# dv_power_chanel.net
KiCad netlist of a schematic drawn in Altium Designer
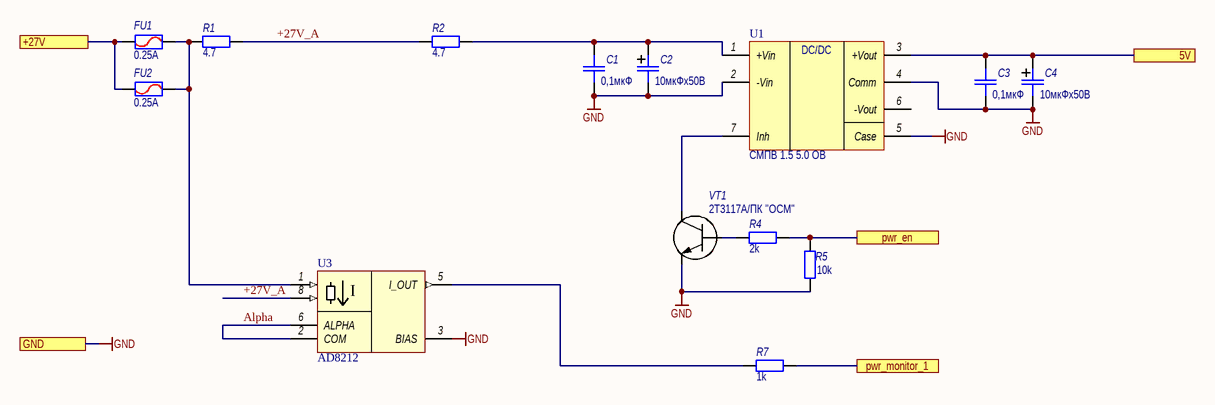
[diagram p0: dv_power_chanel_ВП.SchDoc]

(export (version "E")
  (design (tool "Eeschema 10.0.6"))
  (components
    (comp (ref "C1")
      (value "0,1мкФ")
      (footprint "SMD_0805")
      (description "Capacitor")
      (libsource (lib "Passive") (part "Capacitor"))
    )
    (comp (ref "C2")
      (value "10мкФх50В")
      (footprint "SMD_size_B")
      (description "Polarized capacitor")
      (libsource (lib "Passive") (part "Capacitor_pol"))
    )
    (comp (ref "C3")
      (value "0,1мкФ")
      (footprint "SMD_0805")
      (description "Capacitor")
      (libsource (lib "Passive") (part "Capacitor"))
    )
    (comp (ref "C4")
      (value "10мкФх50В")
      (footprint "SMD_size_B")
      (description "Polarized capacitor")
      (libsource (lib "Passive") (part "Capacitor_pol"))
    )
    (comp (ref "FU1")
      (value "0.25A")
      (footprint "VP1-2")
      (description "Предохранитель плавкий")
      (fields (field (name "Comment") "VP1-2"))
      (libsource (lib "Fuse") (part "VP1-2"))
    )
    (comp (ref "FU2")
      (value "0.25A")
      (footprint "VP1-2")
      (description "Предохранитель плавкий")
      (fields (field (name "Comment") "VP1-2"))
      (libsource (lib "Fuse") (part "VP1-2"))
    )
    (comp (ref "R1")
      (value "4.7")
      (footprint "SMD_0805")
      (description "Resistor")
      (libsource (lib "") (part "Resistor_2"))
    )
    (comp (ref "R2")
      (value "4.7")
      (footprint "SMD_0805")
      (description "Resistor")
      (libsource (lib "") (part "Resistor_2"))
    )
    (comp (ref "R4")
      (value "2k")
      (footprint "SMD_0805")
      (description "Resistor")
      (libsource (lib "Passive") (part "Resistor"))
    )
    (comp (ref "R5")
      (value "10k")
      (footprint "SMD_0805")
      (description "Resistor")
      (libsource (lib "") (part "Resistor_1"))
    )
    (comp (ref "R7")
      (value "1k")
      (footprint "SMD_0805")
      (description "Resistor")
      (libsource (lib "Passive") (part "Resistor"))
    )
    (comp (ref "U1")
      (value "SLH28xx")
      (footprint "SLH28xx")
      (description "DC-DC")
      (fields (field (name "ALTIUM_UNNAMED_1") "СМПВ 1.5 5.0 ОВ"))
      (libsource (lib "DC_DC") (part "SLH28xx"))
    )
    (comp (ref "U3")
      (value "AD8212")
      (footprint "MSOP-8")
      (description "Current shunt monitor")
      (libsource (lib "Power_Monitor") (part "AD8212"))
    )
    (comp (ref "VT1")
      (value "2T3117A")
      (footprint "TO-18")
      (description "Кремниевый биполярный\r\nэпитаксиально-планарный\r\nn-p-n транзистор")
      (fields (field (name "НАИМЕНОВАНИЕ") "2Т3117А/ПК \"ОСМ\""))
      (libsource (lib "Transistor") (part "2T3117A"))
    )
  )
  (nets
    (net (code "1") (name "/+27V") (class "Default")
      (node (ref "FU1") (pin "1") (pinfunction "1_1") (pintype "passive"))
      (node (ref "FU2") (pin "1") (pinfunction "1_1") (pintype "passive"))
    )
    (net (code "2") (name "/+27V_A") (class "Default")
      (node (ref "R1") (pin "1") (pinfunction "1_1") (pintype "passive"))
      (node (ref "R2") (pin "2") (pinfunction "2_2") (pintype "passive"))
      (node (ref "U3") (pin "8") (pinfunction "V_SENSE_8") (pintype "input"))
    )
    (net (code "3") (name "/5V") (class "Default")
      (node (ref "C3") (pin "2") (pinfunction "2_2") (pintype "passive"))
      (node (ref "C4") (pin "1") (pinfunction "1_1") (pintype "passive"))
      (node (ref "U1") (pin "3") (pinfunction "+Vout_3") (pintype "open_collector"))
    )
    (net (code "4") (name "/Alpha") (class "Default")
      (node (ref "U3") (pin "2") (pinfunction "COM_2") (pintype "open_collector"))
      (node (ref "U3") (pin "6") (pinfunction "ALPHA_6") (pintype "open_collector"))
    )
    (net (code "5") (name "/pwr_en") (class "Default")
      (node (ref "R4") (pin "2") (pinfunction "2_2") (pintype "passive"))
      (node (ref "R5") (pin "2") (pinfunction "2_2") (pintype "passive"))
    )
    (net (code "6") (name "/pwr_monitor_1") (class "Default")
      (node (ref "R7") (pin "2") (pinfunction "2_2") (pintype "passive"))
    )
    (net (code "7") (name "GND") (class "Default")
      (node (ref "C1") (pin "1") (pinfunction "1_1") (pintype "passive"))
      (node (ref "C2") (pin "2") (pinfunction "2_2") (pintype "passive"))
      (node (ref "C3") (pin "1") (pinfunction "1_1") (pintype "passive"))
      (node (ref "C4") (pin "2") (pinfunction "2_2") (pintype "passive"))
      (node (ref "R5") (pin "1") (pinfunction "1_1") (pintype "passive"))
      (node (ref "U1") (pin "2") (pinfunction "-Vin_2") (pintype "open_collector"))
      (node (ref "U1") (pin "4") (pinfunction "Comm_4") (pintype "open_collector"))
      (node (ref "U1") (pin "5") (pinfunction "Case_5") (pintype "passive"))
      (node (ref "U3") (pin "3") (pinfunction "BIAS_3") (pintype "open_collector"))
      (node (ref "VT1") (pin "1") (pinfunction "EMITTER_1") (pintype "passive"))
    )
    (net (code "8") (name "Net-(U1-+Vin)") (class "Default")
      (node (ref "C1") (pin "2") (pinfunction "2_2") (pintype "passive"))
      (node (ref "C2") (pin "1") (pinfunction "1_1") (pintype "passive"))
      (node (ref "R2") (pin "1") (pinfunction "1_1") (pintype "passive"))
      (node (ref "U1") (pin "1") (pinfunction "+Vin_1") (pintype "open_collector"))
    )
    (net (code "9") (name "Net-(U1-Inh)") (class "Default")
      (node (ref "U1") (pin "7") (pinfunction "Inh_7") (pintype "open_collector"))
      (node (ref "VT1") (pin "3") (pinfunction "COLLECTOR_3") (pintype "passive"))
    )
    (net (code "10") (name "Net-(U3-I_OUT)") (class "Default")
      (node (ref "R7") (pin "1") (pinfunction "1_1") (pintype "passive"))
      (node (ref "U3") (pin "5") (pinfunction "I_OUT_5") (pintype "output"))
    )
    (net (code "11") (name "Net-(U3-V+)") (class "Default")
      (node (ref "FU1") (pin "2") (pinfunction "2_2") (pintype "passive"))
      (node (ref "FU2") (pin "2") (pinfunction "2_2") (pintype "passive"))
      (node (ref "R1") (pin "2") (pinfunction "2_2") (pintype "passive"))
      (node (ref "U3") (pin "1") (pinfunction "V+_1") (pintype "input"))
    )
    (net (code "12") (name "Net-(VT1-BASE)") (class "Default")
      (node (ref "R4") (pin "1") (pinfunction "1_1") (pintype "passive"))
      (node (ref "VT1") (pin "2") (pinfunction "BASE_2") (pintype "passive"))
    )
    (net (code "13") (name "unconnected-(U1--Vout-Pad6)") (class "Default")
      (node (ref "U1") (pin "6") (pinfunction "-Vout_6") (pintype "open_collector"))
    )
  )
)
